# simon.net
KiCad netlist of a schematic drawn in EAGLE
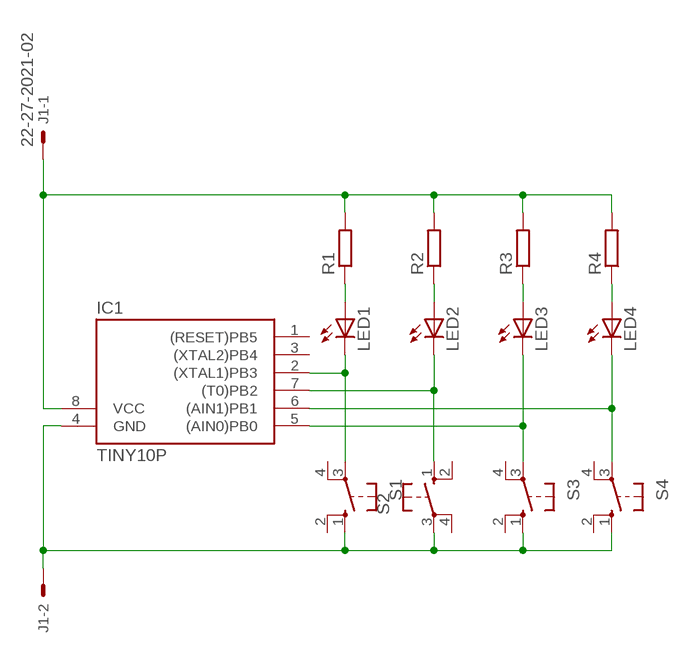
[diagram p0: schematic, sheet 1]

(export (version "E")
  (design (tool "Eeschema 10.0.6"))
  (components
    (comp (ref "IC1")
      (value "TINY10P")
      (footprint "eagle-import:DIL08")
      (libsource (lib "eagle-import") (part "TINY10P"))
    )
    (comp (ref "J1")
      (value "22-27-2021-02")
      (footprint "eagle-import:6410-02")
      (libsource (lib "eagle-import") (part "22-?-0227-2021"))
    )
    (comp (ref "LED1")
      (value "LED3MM")
      (footprint "eagle-import:LED3MM")
      (libsource (lib "eagle-import") (part "LED3MM"))
    )
    (comp (ref "LED2")
      (value "LED3MM")
      (footprint "eagle-import:LED3MM")
      (libsource (lib "eagle-import") (part "LED3MM"))
    )
    (comp (ref "LED3")
      (value "LED3MM")
      (footprint "eagle-import:LED3MM")
      (libsource (lib "eagle-import") (part "LED3MM"))
    )
    (comp (ref "LED4")
      (value "LED3MM")
      (footprint "eagle-import:LED3MM")
      (libsource (lib "eagle-import") (part "LED3MM"))
    )
    (comp (ref "R1")
      (value "R-EU_0204/2V")
      (footprint "eagle-import:0204V")
      (libsource (lib "eagle-import") (part "R-EU_0204/2V"))
    )
    (comp (ref "R2")
      (value "R-EU_0204/2V")
      (footprint "eagle-import:0204V")
      (libsource (lib "eagle-import") (part "R-EU_0204/2V"))
    )
    (comp (ref "R3")
      (value "R-EU_0204/2V")
      (footprint "eagle-import:0204V")
      (libsource (lib "eagle-import") (part "R-EU_0204/2V"))
    )
    (comp (ref "R4")
      (value "R-EU_0204/2V")
      (footprint "eagle-import:0204V")
      (libsource (lib "eagle-import") (part "R-EU_0204/2V"))
    )
    (comp (ref "S1")
      (value "10-XX")
      (footprint "eagle-import:B3F-10XX")
      (fields (field (name "MPN") "B3F-1000"))
      (libsource (lib "eagle-import") (part "10-XX"))
    )
    (comp (ref "S2")
      (value "10-XX")
      (footprint "eagle-import:B3F-10XX")
      (fields (field (name "MPN") "B3F-1000"))
      (libsource (lib "eagle-import") (part "10-XX"))
    )
    (comp (ref "S3")
      (value "10-XX")
      (footprint "eagle-import:B3F-10XX")
      (fields (field (name "MPN") "B3F-1000"))
      (libsource (lib "eagle-import") (part "10-XX"))
    )
    (comp (ref "S4")
      (value "10-XX")
      (footprint "eagle-import:B3F-10XX")
      (fields (field (name "MPN") "B3F-1000"))
      (libsource (lib "eagle-import") (part "10-XX"))
    )
  )
  (nets
    (net (code "1") (name "Net-(IC1-(AIN0)PB0)") (class "Default")
      (node (ref "IC1") (pin "5") (pinfunction "(AIN0)PB0_5") (pintype "bidirectional"))
      (node (ref "LED3") (pin "K") (pinfunction "C_K") (pintype "passive"))
      (node (ref "S3") (pin "3") (pinfunction "P_3") (pintype "passive"))
    )
    (net (code "2") (name "Net-(IC1-(AIN1)PB1)") (class "Default")
      (node (ref "IC1") (pin "6") (pinfunction "(AIN1)PB1_6") (pintype "bidirectional"))
      (node (ref "LED4") (pin "K") (pinfunction "C_K") (pintype "passive"))
      (node (ref "S4") (pin "3") (pinfunction "P_3") (pintype "passive"))
    )
    (net (code "3") (name "Net-(IC1-(T0)PB2)") (class "Default")
      (node (ref "IC1") (pin "7") (pinfunction "(T0)PB2_7") (pintype "bidirectional"))
      (node (ref "LED2") (pin "K") (pinfunction "C_K") (pintype "passive"))
      (node (ref "S2") (pin "1") (pinfunction "S_1") (pintype "passive"))
    )
    (net (code "4") (name "Net-(IC1-(XTAL1)PB3)") (class "Default")
      (node (ref "IC1") (pin "2") (pinfunction "(XTAL1)PB3_2") (pintype "bidirectional"))
      (node (ref "LED1") (pin "K") (pinfunction "C_K") (pintype "passive"))
      (node (ref "S1") (pin "3") (pinfunction "P_3") (pintype "passive"))
    )
    (net (code "5") (name "Net-(IC1-GND)") (class "Default")
      (node (ref "IC1") (pin "4") (pinfunction "GND_4") (pintype "power_in"))
      (node (ref "J1") (pin "2") (pinfunction "S_2") (pintype "passive"))
      (node (ref "S1") (pin "1") (pinfunction "S_1") (pintype "passive"))
      (node (ref "S2") (pin "3") (pinfunction "P_3") (pintype "passive"))
      (node (ref "S3") (pin "1") (pinfunction "S_1") (pintype "passive"))
      (node (ref "S4") (pin "1") (pinfunction "S_1") (pintype "passive"))
    )
    (net (code "6") (name "Net-(IC1-VCC)") (class "Default")
      (node (ref "IC1") (pin "8") (pinfunction "VCC_8") (pintype "power_in"))
      (node (ref "J1") (pin "1") (pinfunction "S_1") (pintype "passive"))
      (node (ref "R1") (pin "2") (pinfunction "2_2") (pintype "passive"))
      (node (ref "R2") (pin "2") (pinfunction "2_2") (pintype "passive"))
      (node (ref "R3") (pin "2") (pinfunction "2_2") (pintype "passive"))
      (node (ref "R4") (pin "2") (pinfunction "2_2") (pintype "passive"))
    )
    (net (code "7") (name "Net-(LED1-PadA)") (class "Default")
      (node (ref "LED1") (pin "A") (pinfunction "A_A") (pintype "passive"))
      (node (ref "R1") (pin "1") (pinfunction "1_1") (pintype "passive"))
    )
    (net (code "8") (name "Net-(LED2-PadA)") (class "Default")
      (node (ref "LED2") (pin "A") (pinfunction "A_A") (pintype "passive"))
      (node (ref "R2") (pin "1") (pinfunction "1_1") (pintype "passive"))
    )
    (net (code "9") (name "Net-(LED3-PadA)") (class "Default")
      (node (ref "LED3") (pin "A") (pinfunction "A_A") (pintype "passive"))
      (node (ref "R3") (pin "1") (pinfunction "1_1") (pintype "passive"))
    )
    (net (code "10") (name "Net-(LED4-PadA)") (class "Default")
      (node (ref "LED4") (pin "A") (pinfunction "A_A") (pintype "passive"))
      (node (ref "R4") (pin "1") (pinfunction "1_1") (pintype "passive"))
    )
    (net (code "11") (name "unconnected-(IC1-(RESET)PB5-Pad1)") (class "Default")
      (node (ref "IC1") (pin "1") (pinfunction "(RESET)PB5_1") (pintype "bidirectional"))
    )
    (net (code "12") (name "unconnected-(IC1-(XTAL2)PB4-Pad3)") (class "Default")
      (node (ref "IC1") (pin "3") (pinfunction "(XTAL2)PB4_3") (pintype "bidirectional"))
    )
    (net (code "13") (name "unconnected-(S1-P1-Pad4)") (class "Default")
      (node (ref "S1") (pin "4") (pinfunction "P1_4") (pintype "passive"))
    )
    (net (code "14") (name "unconnected-(S1-S1-Pad2)") (class "Default")
      (node (ref "S1") (pin "2") (pinfunction "S1_2") (pintype "passive"))
    )
    (net (code "15") (name "unconnected-(S2-P1-Pad4)") (class "Default")
      (node (ref "S2") (pin "4") (pinfunction "P1_4") (pintype "passive"))
    )
    (net (code "16") (name "unconnected-(S2-S1-Pad2)") (class "Default")
      (node (ref "S2") (pin "2") (pinfunction "S1_2") (pintype "passive"))
    )
    (net (code "17") (name "unconnected-(S3-P1-Pad4)") (class "Default")
      (node (ref "S3") (pin "4") (pinfunction "P1_4") (pintype "passive"))
    )
    (net (code "18") (name "unconnected-(S3-S1-Pad2)") (class "Default")
      (node (ref "S3") (pin "2") (pinfunction "S1_2") (pintype "passive"))
    )
    (net (code "19") (name "unconnected-(S4-P1-Pad4)") (class "Default")
      (node (ref "S4") (pin "4") (pinfunction "P1_4") (pintype "passive"))
    )
    (net (code "20") (name "unconnected-(S4-S1-Pad2)") (class "Default")
      (node (ref "S4") (pin "2") (pinfunction "S1_2") (pintype "passive"))
    )
  )
)
